# FanPWM.net
KiCad netlist of a schematic drawn in Altium Designer
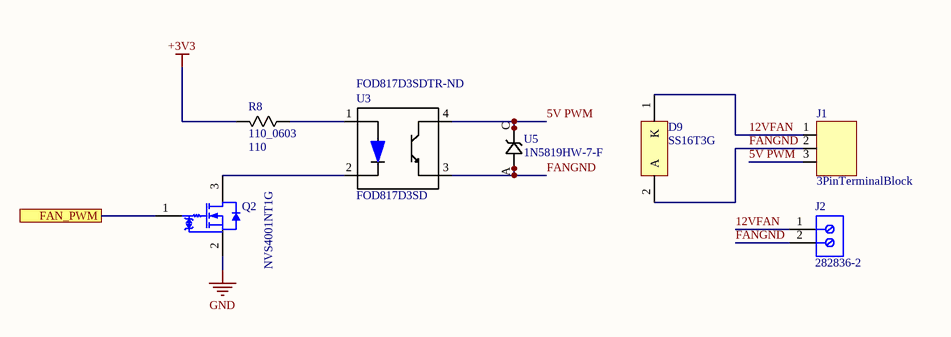
[diagram p0: FanPWM.SchDoc]

(export (version "E")
  (design (tool "Eeschema 10.0.6"))
  (components
    (comp (ref "D9")
      (value "SS16T3G")
      (footprint "ONSC-SMA-2-403D-02_V")
      (description "Schottky Power Rectifier, 2-Pin SMA, Pb-Free, Tape and Reel")
      (fields (field (name "MANUFACTURER") "On Semiconductor"))
      (libsource (lib "ON Semi Schottky Diodes & Schottky Rectifiers") (part "SS16T3G"))
    )
    (comp (ref "J1")
      (value "3PinTerminalBlock")
      (footprint "3 POS 5mm Pitch")
      (description "3 Position terminal block")
      (libsource (lib "Connectors") (part "3PinTerminalBlock"))
    )
    (comp (ref "J2")
      (value "282836-2")
      (footprint "TECO-282836-2_V")
      (description "Female Header, Pitch 5 mm, 1 x 2 Position, Height 10 mm, Tail Length 3.5 mm, Rohs, Bulk")
      (fields (field (name "VOLTAGE") "300V"))
      (libsource (lib "TE Terminal Blocks and Strips") (part "282836-2"))
    )
    (comp (ref "Q2")
      (value "NVS4001NT1G")
      (footprint "ONSC-SC-70-3-419-04_V")
      (description "Small Signal MOSFET, 30 V, 270 mA, N-Channel, 3-Pin SC70, Pb-Free, Tape and Reel")
      (fields (field (name "MANUFACTURER") "On Semiconductor"))
      (libsource (lib "ON Semi MOSFETs") (part "NVS4001NT1G"))
    )
    (comp (ref "R8")
      (value "110_0603")
      (footprint "0603")
      (fields
        (field (name "MANUFACTURER") "Vishay")
        (field (name "MANUFACTURER PART NUMBER") "CRCW0603110RFKEA")
        (field (name "TOLERANCE") "1%")
        (field (name "RESISTANCE") "110")
      )
      (libsource (lib "Resistors") (part "110_0603"))
    )
    (comp (ref "U3")
      (value "FOD817D3SD")
      (footprint "FOD817D3SD")
      (description "OPTOISOLATOR 5KV TRANSISTOR 4SMD 20mA/1.2V saturation")
      (fields
        (field (name "MANUFACTURER") "ON Semiconductor / Fairchild")
        (field (name "SUPPLIER PART NUMBER 1") "FOD817D3SDTR-ND")
      )
      (libsource (lib "Optocouplers") (part "FOD817D3SD"))
    )
    (comp (ref "U5")
      (value "1N5819HW-7-F")
      (footprint "1N5819HW-7-F")
      (description "DIODE SCHOTTKY 40V 1A SOD123")
      (libsource (lib "Diodes") (part "1N5819HW-7-F"))
    )
  )
  (nets
    (net (code "1") (name "+3V3") (class "Default")
      (node (ref "R8") (pin "1") (pinfunction "1_1") (pintype "passive"))
    )
    (net (code "2") (name "/5V PWM") (class "Default")
      (node (ref "J1") (pin "3") (pintype "passive"))
      (node (ref "U3") (pin "4") (pinfunction "COLLECTOR_4") (pintype "bidirectional"))
      (node (ref "U5") (pin "C") (pintype "passive"))
    )
    (net (code "3") (name "/12VFAN") (class "Default")
      (node (ref "D9") (pin "1") (pinfunction "K_1") (pintype "passive"))
      (node (ref "J1") (pin "1") (pintype "passive"))
      (node (ref "J2") (pin "1") (pinfunction "1_1") (pintype "passive"))
    )
    (net (code "4") (name "/FANGND") (class "Default")
      (node (ref "D9") (pin "2") (pinfunction "A_2") (pintype "passive"))
      (node (ref "J1") (pin "2") (pintype "passive"))
      (node (ref "J2") (pin "2") (pinfunction "2_2") (pintype "passive"))
      (node (ref "U3") (pin "3") (pinfunction "EMITER_3") (pintype "bidirectional"))
      (node (ref "U5") (pin "A") (pintype "passive"))
    )
    (net (code "5") (name "/FAN_PWM") (class "Default")
      (node (ref "Q2") (pin "1") (pinfunction "G_1") (pintype "passive"))
    )
    (net (code "6") (name "GND") (class "Default")
      (node (ref "Q2") (pin "2") (pinfunction "S_2") (pintype "passive"))
    )
    (net (code "7") (name "Net-(Q2-D)") (class "Default")
      (node (ref "Q2") (pin "3") (pinfunction "D_3") (pintype "passive"))
      (node (ref "U3") (pin "2") (pinfunction "CATHODE_2") (pintype "bidirectional"))
    )
    (net (code "8") (name "Net-(U3-ANODE)") (class "Default")
      (node (ref "R8") (pin "2") (pinfunction "2_2") (pintype "passive"))
      (node (ref "U3") (pin "1") (pinfunction "ANODE_1") (pintype "bidirectional"))
    )
  )
)
